# Flash_Fashion_Schematic.net
KiCad netlist of a schematic drawn in EAGLE
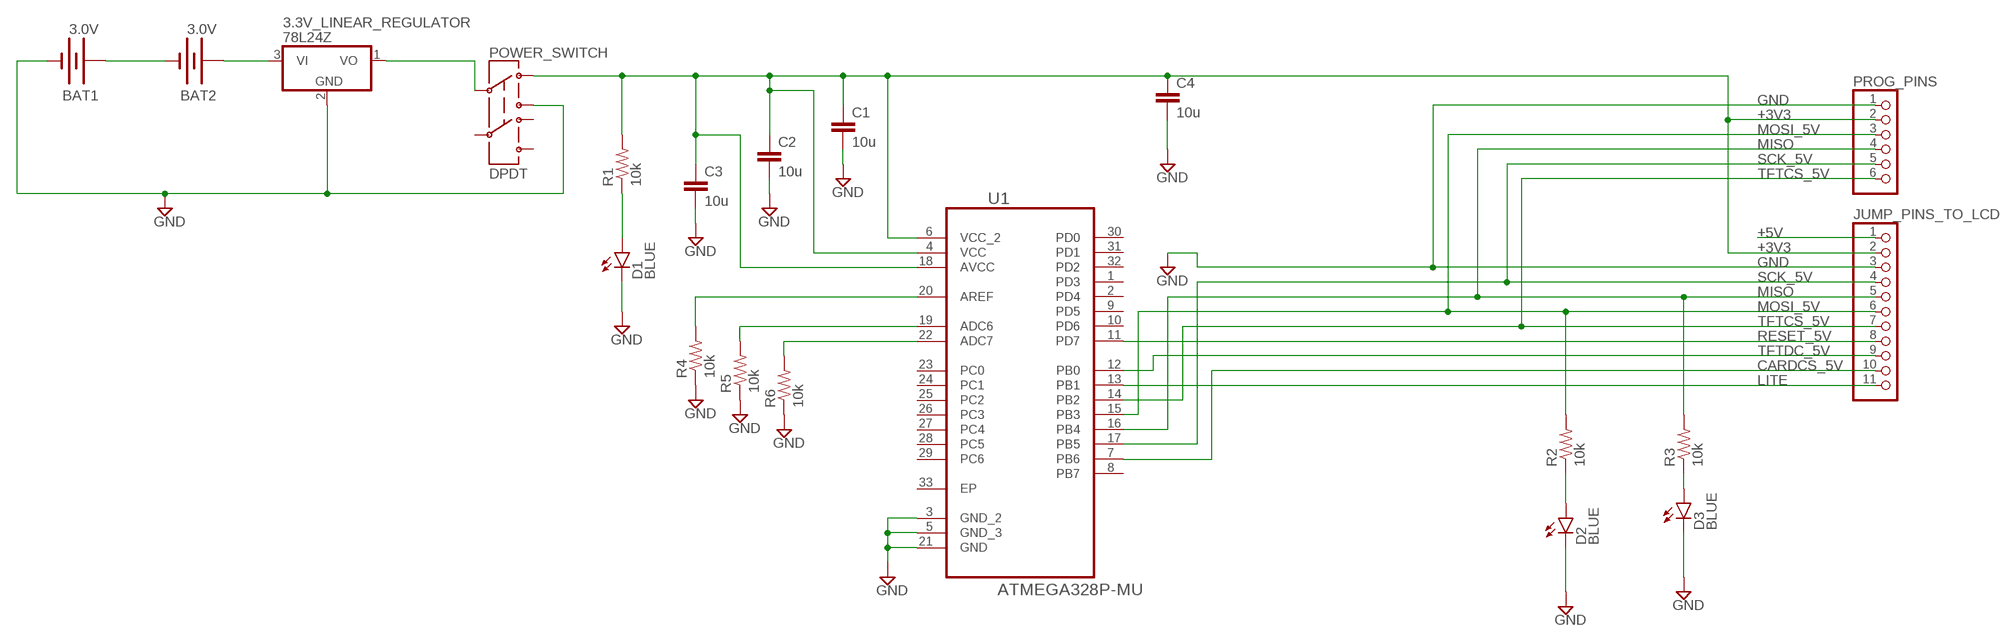
[diagram p0: schematic, sheet 1]

(export (version "E")
  (design (tool "Eeschema 10.0.6"))
  (components
    (comp (ref "3.3V_LINEAR_REGULATOR")
      (value "78L24Z")
      (footprint "eagle-import:TO92")
      (libsource (lib "eagle-import") (part "78ZL24"))
    )
    (comp (ref "BAT1")
      (value "3.0V")
      (footprint "eagle-import:BATTCON_245MM_PTH")
      (libsource (lib "eagle-import") (part "BATTERY245PTH"))
    )
    (comp (ref "BAT2")
      (value "3.0V")
      (footprint "eagle-import:BATTCON_245MM_PTH")
      (libsource (lib "eagle-import") (part "BATTERY245PTH"))
    )
    (comp (ref "C1")
      (value "10u")
      (footprint "eagle-import:1206")
      (libsource (lib "eagle-import") (part "CAP1206"))
    )
    (comp (ref "C2")
      (value "10u")
      (footprint "eagle-import:1206")
      (libsource (lib "eagle-import") (part "CAP1206"))
    )
    (comp (ref "C3")
      (value "10u")
      (footprint "eagle-import:1206")
      (libsource (lib "eagle-import") (part "CAP1206"))
    )
    (comp (ref "C4")
      (value "10u")
      (footprint "eagle-import:1206")
      (libsource (lib "eagle-import") (part "CAP1206"))
    )
    (comp (ref "D1")
      (value "BLUE")
      (footprint "eagle-import:LED-1206")
      (libsource (lib "eagle-import") (part "LED-BLUE1206"))
    )
    (comp (ref "D2")
      (value "BLUE")
      (footprint "eagle-import:LED-1206")
      (libsource (lib "eagle-import") (part "LED-BLUE1206"))
    )
    (comp (ref "D3")
      (value "BLUE")
      (footprint "eagle-import:LED-1206")
      (libsource (lib "eagle-import") (part "LED-BLUE1206"))
    )
    (comp (ref "JUMP_PINS_TO_LCD")
      (value "HEADER-1X1176MIL")
      (footprint "eagle-import:1X11_ROUND_76")
      (libsource (lib "eagle-import") (part "HEADER-1X1176MIL"))
    )
    (comp (ref "POWER_SWITCH")
      (value "DPDT")
      (footprint "eagle-import:AYZ0202")
      (libsource (lib "eagle-import") (part "SWITCH-DPDTAYZ0202"))
    )
    (comp (ref "PROG_PINS")
      (value "PINHD-1X6-3.5MM")
      (footprint "eagle-import:1X06-3.5MM")
      (libsource (lib "eagle-import") (part "PINHD-1X6-3.5MM"))
    )
    (comp (ref "R1")
      (value "10k")
      (footprint "eagle-import:1206")
      (libsource (lib "eagle-import") (part "RESISTOR1206"))
    )
    (comp (ref "R2")
      (value "10k")
      (footprint "eagle-import:1206")
      (libsource (lib "eagle-import") (part "RESISTOR1206"))
    )
    (comp (ref "R3")
      (value "10k")
      (footprint "eagle-import:1206")
      (libsource (lib "eagle-import") (part "RESISTOR1206"))
    )
    (comp (ref "R4")
      (value "10k")
      (footprint "eagle-import:1206")
      (libsource (lib "eagle-import") (part "RESISTOR1206"))
    )
    (comp (ref "R5")
      (value "10k")
      (footprint "eagle-import:1206")
      (libsource (lib "eagle-import") (part "RESISTOR1206"))
    )
    (comp (ref "R6")
      (value "10k")
      (footprint "eagle-import:1206")
      (libsource (lib "eagle-import") (part "RESISTOR1206"))
    )
    (comp (ref "U1")
      (value "ATMEGA328P-MU")
      (footprint "eagle-import:QFN50P500X500X100-33N")
      (libsource (lib "eagle-import") (part "ATMEGA328P-MU"))
    )
  )
  (nets
    (net (code "1") (name "/+3V3") (class "Default")
      (node (ref "C1") (pin "1") (pinfunction "1_1") (pintype "passive"))
      (node (ref "C2") (pin "1") (pinfunction "1_1") (pintype "passive"))
      (node (ref "C3") (pin "1") (pinfunction "1_1") (pintype "passive"))
      (node (ref "C4") (pin "1") (pinfunction "1_1") (pintype "passive"))
      (node (ref "JUMP_PINS_TO_LCD") (pin "2") (pinfunction "2_2") (pintype "passive"))
      (node (ref "POWER_SWITCH") (pin "1") (pinfunction "1_1") (pintype "bidirectional"))
      (node (ref "PROG_PINS") (pin "2") (pinfunction "2_2") (pintype "passive"))
      (node (ref "R1") (pin "2") (pinfunction "2_2") (pintype "passive"))
      (node (ref "U1") (pin "18") (pinfunction "AVCC_18") (pintype "power_in"))
      (node (ref "U1") (pin "4") (pinfunction "VCC_4") (pintype "power_in"))
      (node (ref "U1") (pin "6") (pinfunction "VCC_2_6") (pintype "power_in"))
    )
    (net (code "2") (name "/+5V") (class "Default")
      (node (ref "JUMP_PINS_TO_LCD") (pin "1") (pinfunction "1_1") (pintype "passive"))
    )
    (net (code "3") (name "/CARDCS_5V") (class "Default")
      (node (ref "JUMP_PINS_TO_LCD") (pin "10") (pinfunction "10_10") (pintype "passive"))
      (node (ref "U1") (pin "7") (pinfunction "PB6_7") (pintype "bidirectional"))
    )
    (net (code "4") (name "/LITE") (class "Default")
      (node (ref "JUMP_PINS_TO_LCD") (pin "11") (pinfunction "11_11") (pintype "passive"))
      (node (ref "U1") (pin "13") (pinfunction "PB1_13") (pintype "bidirectional"))
    )
    (net (code "5") (name "/MISO") (class "Default")
      (node (ref "JUMP_PINS_TO_LCD") (pin "5") (pinfunction "5_5") (pintype "passive"))
      (node (ref "PROG_PINS") (pin "4") (pinfunction "4_4") (pintype "passive"))
      (node (ref "R3") (pin "2") (pinfunction "2_2") (pintype "passive"))
      (node (ref "U1") (pin "16") (pinfunction "PB4_16") (pintype "bidirectional"))
    )
    (net (code "6") (name "/MOSI_5V") (class "Default")
      (node (ref "JUMP_PINS_TO_LCD") (pin "6") (pinfunction "6_6") (pintype "passive"))
      (node (ref "PROG_PINS") (pin "3") (pinfunction "3_3") (pintype "passive"))
      (node (ref "R2") (pin "2") (pinfunction "2_2") (pintype "passive"))
      (node (ref "U1") (pin "15") (pinfunction "PB3_15") (pintype "bidirectional"))
    )
    (net (code "7") (name "/RESET_5V") (class "Default")
      (node (ref "JUMP_PINS_TO_LCD") (pin "8") (pinfunction "8_8") (pintype "passive"))
      (node (ref "U1") (pin "11") (pinfunction "PD7_11") (pintype "bidirectional"))
    )
    (net (code "8") (name "/SCK_5V") (class "Default")
      (node (ref "JUMP_PINS_TO_LCD") (pin "4") (pinfunction "4_4") (pintype "passive"))
      (node (ref "PROG_PINS") (pin "5") (pinfunction "5_5") (pintype "passive"))
      (node (ref "U1") (pin "17") (pinfunction "PB5_17") (pintype "bidirectional"))
    )
    (net (code "9") (name "/TFTCS_5V") (class "Default")
      (node (ref "JUMP_PINS_TO_LCD") (pin "7") (pinfunction "7_7") (pintype "passive"))
      (node (ref "PROG_PINS") (pin "6") (pinfunction "6_6") (pintype "passive"))
      (node (ref "U1") (pin "14") (pinfunction "PB2_14") (pintype "bidirectional"))
    )
    (net (code "10") (name "/TFTDC_5V") (class "Default")
      (node (ref "JUMP_PINS_TO_LCD") (pin "9") (pinfunction "9_9") (pintype "passive"))
      (node (ref "U1") (pin "12") (pinfunction "PB0_12") (pintype "bidirectional"))
    )
    (net (code "11") (name "GND") (class "Default")
      (node (ref "3.3V_LINEAR_REGULATOR") (pin "2") (pinfunction "GND_2") (pintype "passive"))
      (node (ref "BAT1") (pin "2") (pinfunction "-_2") (pintype "power_in"))
      (node (ref "C1") (pin "2") (pinfunction "2_2") (pintype "passive"))
      (node (ref "C2") (pin "2") (pinfunction "2_2") (pintype "passive"))
      (node (ref "C3") (pin "2") (pinfunction "2_2") (pintype "passive"))
      (node (ref "C4") (pin "2") (pinfunction "2_2") (pintype "passive"))
      (node (ref "D1") (pin "C") (pinfunction "C_C") (pintype "passive"))
      (node (ref "D2") (pin "C") (pinfunction "C_C") (pintype "passive"))
      (node (ref "D3") (pin "C") (pinfunction "C_C") (pintype "passive"))
      (node (ref "JUMP_PINS_TO_LCD") (pin "3") (pinfunction "3_3") (pintype "passive"))
      (node (ref "POWER_SWITCH") (pin "3") (pinfunction "3_3") (pintype "bidirectional"))
      (node (ref "PROG_PINS") (pin "1") (pinfunction "1_1") (pintype "passive"))
      (node (ref "R4") (pin "1") (pinfunction "1_1") (pintype "passive"))
      (node (ref "R5") (pin "1") (pinfunction "1_1") (pintype "passive"))
      (node (ref "R6") (pin "1") (pinfunction "1_1") (pintype "passive"))
      (node (ref "U1") (pin "21") (pinfunction "GND_21") (pintype "passive"))
      (node (ref "U1") (pin "3") (pinfunction "GND_2_3") (pintype "passive"))
      (node (ref "U1") (pin "5") (pinfunction "GND_3_5") (pintype "passive"))
    )
    (net (code "12") (name "Net-(3.3V_LINEAR_REGULATOR-VI)") (class "Default")
      (node (ref "3.3V_LINEAR_REGULATOR") (pin "3") (pinfunction "VI_3") (pintype "input"))
      (node (ref "BAT2") (pin "3") (pinfunction "+_3") (pintype "power_in"))
    )
    (net (code "13") (name "Net-(3.3V_LINEAR_REGULATOR-VO)") (class "Default")
      (node (ref "3.3V_LINEAR_REGULATOR") (pin "1") (pinfunction "VO_1") (pintype "passive"))
      (node (ref "POWER_SWITCH") (pin "2") (pinfunction "2_2") (pintype "bidirectional"))
    )
    (net (code "14") (name "Net-(BAT1-+)") (class "Default")
      (node (ref "BAT1") (pin "3") (pinfunction "+_3") (pintype "power_in"))
      (node (ref "BAT2") (pin "2") (pinfunction "-_2") (pintype "power_in"))
    )
    (net (code "15") (name "Net-(D1-PadA)") (class "Default")
      (node (ref "D1") (pin "A") (pinfunction "A_A") (pintype "passive"))
      (node (ref "R1") (pin "1") (pinfunction "1_1") (pintype "passive"))
    )
    (net (code "16") (name "Net-(D2-PadA)") (class "Default")
      (node (ref "D2") (pin "A") (pinfunction "A_A") (pintype "passive"))
      (node (ref "R2") (pin "1") (pinfunction "1_1") (pintype "passive"))
    )
    (net (code "17") (name "Net-(D3-PadA)") (class "Default")
      (node (ref "D3") (pin "A") (pinfunction "A_A") (pintype "passive"))
      (node (ref "R3") (pin "1") (pinfunction "1_1") (pintype "passive"))
    )
    (net (code "18") (name "Net-(U1-ADC6)") (class "Default")
      (node (ref "R5") (pin "2") (pinfunction "2_2") (pintype "passive"))
      (node (ref "U1") (pin "19") (pinfunction "ADC6_19") (pintype "input"))
    )
    (net (code "19") (name "Net-(U1-ADC7)") (class "Default")
      (node (ref "R6") (pin "2") (pinfunction "2_2") (pintype "passive"))
      (node (ref "U1") (pin "22") (pinfunction "ADC7_22") (pintype "input"))
    )
    (net (code "20") (name "Net-(U1-AREF)") (class "Default")
      (node (ref "R4") (pin "2") (pinfunction "2_2") (pintype "passive"))
      (node (ref "U1") (pin "20") (pinfunction "AREF_20") (pintype "input"))
    )
    (net (code "21") (name "unconnected-(POWER_SWITCH-Pad4)") (class "Default")
      (node (ref "POWER_SWITCH") (pin "4") (pinfunction "4_4") (pintype "bidirectional"))
    )
    (net (code "22") (name "unconnected-(POWER_SWITCH-Pad5)") (class "Default")
      (node (ref "POWER_SWITCH") (pin "5") (pinfunction "5_5") (pintype "bidirectional"))
    )
    (net (code "23") (name "unconnected-(POWER_SWITCH-Pad6)") (class "Default")
      (node (ref "POWER_SWITCH") (pin "6") (pinfunction "6_6") (pintype "bidirectional"))
    )
    (net (code "24") (name "unconnected-(U1-EP-Pad33)") (class "Default")
      (node (ref "U1") (pin "33") (pinfunction "EP_33") (pintype "passive"))
    )
    (net (code "25") (name "unconnected-(U1-PB7-Pad8)") (class "Default")
      (node (ref "U1") (pin "8") (pinfunction "PB7_8") (pintype "bidirectional"))
    )
    (net (code "26") (name "unconnected-(U1-PC0-Pad23)") (class "Default")
      (node (ref "U1") (pin "23") (pinfunction "PC0_23") (pintype "bidirectional"))
    )
    (net (code "27") (name "unconnected-(U1-PC1-Pad24)") (class "Default")
      (node (ref "U1") (pin "24") (pinfunction "PC1_24") (pintype "bidirectional"))
    )
    (net (code "28") (name "unconnected-(U1-PC2-Pad25)") (class "Default")
      (node (ref "U1") (pin "25") (pinfunction "PC2_25") (pintype "bidirectional"))
    )
    (net (code "29") (name "unconnected-(U1-PC3-Pad26)") (class "Default")
      (node (ref "U1") (pin "26") (pinfunction "PC3_26") (pintype "bidirectional"))
    )
    (net (code "30") (name "unconnected-(U1-PC4-Pad27)") (class "Default")
      (node (ref "U1") (pin "27") (pinfunction "PC4_27") (pintype "bidirectional"))
    )
    (net (code "31") (name "unconnected-(U1-PC5-Pad28)") (class "Default")
      (node (ref "U1") (pin "28") (pinfunction "PC5_28") (pintype "bidirectional"))
    )
    (net (code "32") (name "unconnected-(U1-PC6-Pad29)") (class "Default")
      (node (ref "U1") (pin "29") (pinfunction "PC6_29") (pintype "bidirectional"))
    )
    (net (code "33") (name "unconnected-(U1-PD0-Pad30)") (class "Default")
      (node (ref "U1") (pin "30") (pinfunction "PD0_30") (pintype "bidirectional"))
    )
    (net (code "34") (name "unconnected-(U1-PD1-Pad31)") (class "Default")
      (node (ref "U1") (pin "31") (pinfunction "PD1_31") (pintype "bidirectional"))
    )
    (net (code "35") (name "unconnected-(U1-PD2-Pad32)") (class "Default")
      (node (ref "U1") (pin "32") (pinfunction "PD2_32") (pintype "bidirectional"))
    )
    (net (code "36") (name "unconnected-(U1-PD3-Pad1)") (class "Default")
      (node (ref "U1") (pin "1") (pinfunction "PD3_1") (pintype "bidirectional"))
    )
    (net (code "37") (name "unconnected-(U1-PD4-Pad2)") (class "Default")
      (node (ref "U1") (pin "2") (pinfunction "PD4_2") (pintype "bidirectional"))
    )
    (net (code "38") (name "unconnected-(U1-PD5-Pad9)") (class "Default")
      (node (ref "U1") (pin "9") (pinfunction "PD5_9") (pintype "bidirectional"))
    )
    (net (code "39") (name "unconnected-(U1-PD6-Pad10)") (class "Default")
      (node (ref "U1") (pin "10") (pinfunction "PD6_10") (pintype "bidirectional"))
    )
  )
)
